# rev02_4.net
KiCad netlist of a schematic drawn in Altium Designer
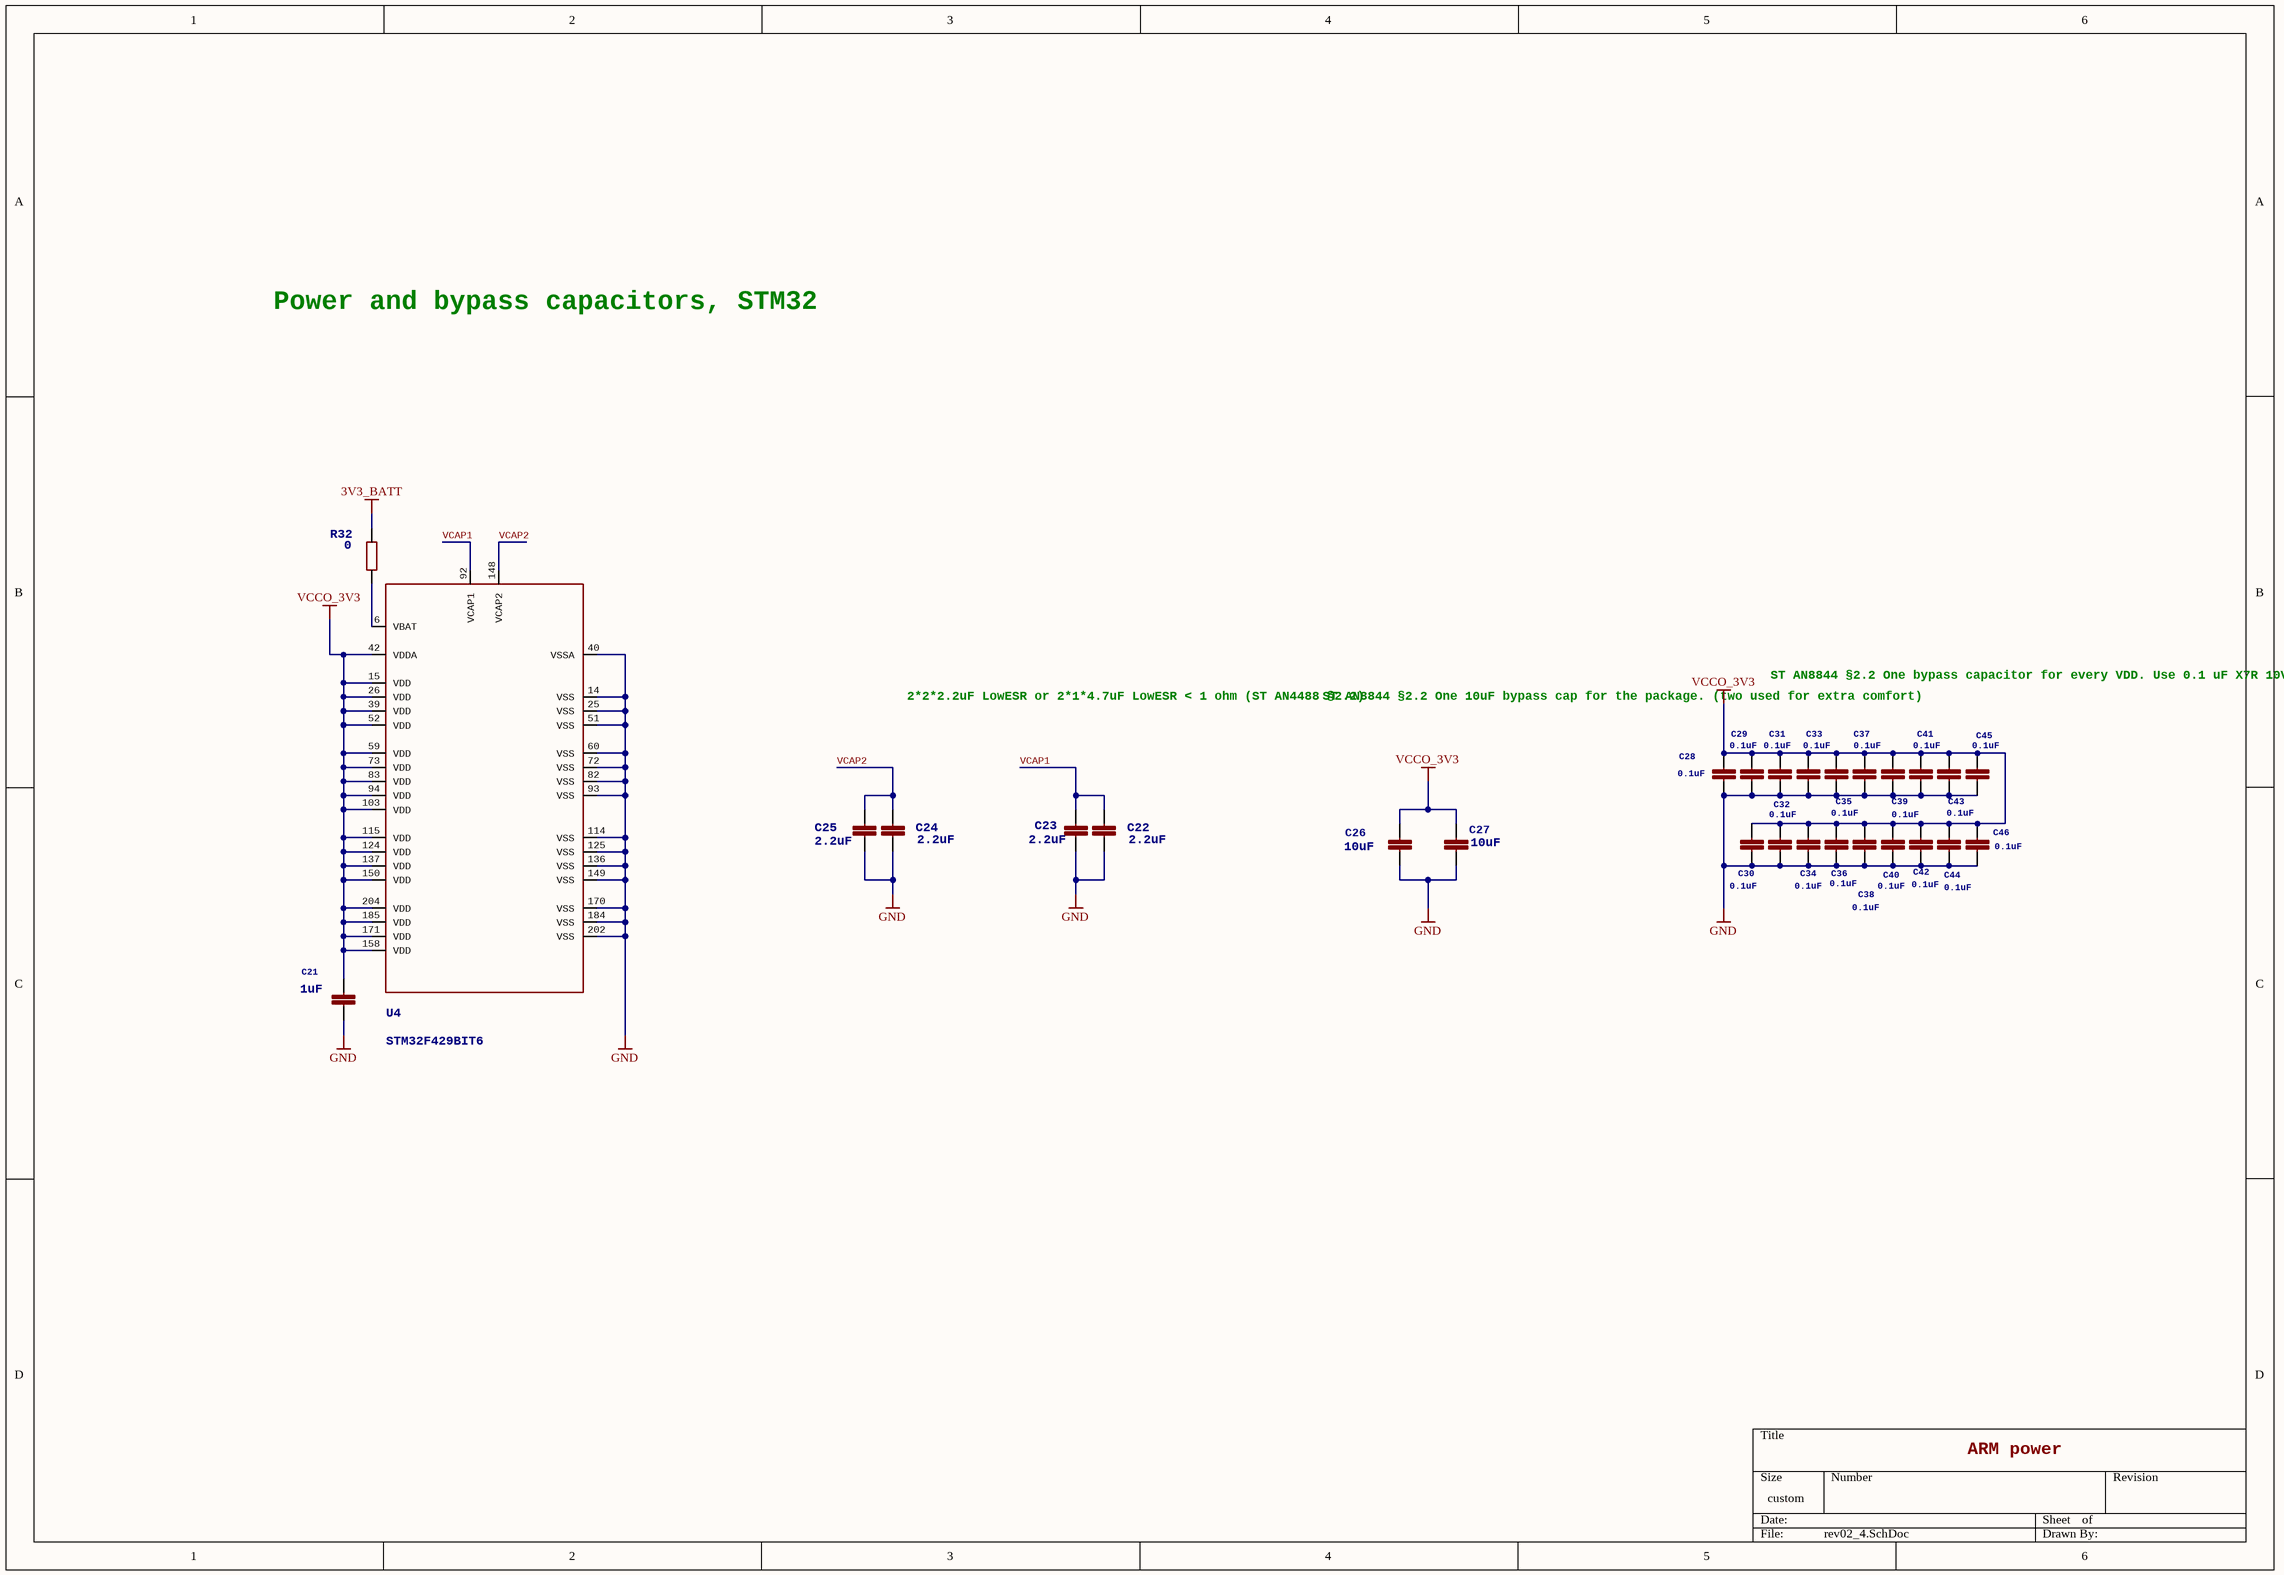
[diagram p0: rev02_4.SchDoc]

(export (version "E")
  (design (tool "Eeschema 10.0.6"))
  (components
    (comp (ref "C21")
      (value "1uF")
      (footprint "C_0603")
      (description "0603 CAPACITOR")
      (libsource (lib "") (part "C-EUC0603_1"))
    )
    (comp (ref "C22")
      (value "2.2uF")
      (footprint "C_0603")
      (description "0603 CAPACITOR")
      (libsource (lib "resistor") (part "C-EUC0603"))
    )
    (comp (ref "C23")
      (value "2.2uF")
      (footprint "C_0603")
      (description "0603 CAPACITOR")
      (libsource (lib "resistor") (part "C-EUC0603"))
    )
    (comp (ref "C24")
      (value "2.2uF")
      (footprint "C_0603")
      (description "0603 CAPACITOR")
      (libsource (lib "resistor") (part "C-EUC0603"))
    )
    (comp (ref "C25")
      (value "2.2uF")
      (footprint "C_0603")
      (description "0603 CAPACITOR")
      (libsource (lib "resistor") (part "C-EUC0603"))
    )
    (comp (ref "C26")
      (value "10uF")
      (footprint "C_0805")
      (description "0805 CAPACITOR")
      (libsource (lib "resistor") (part "C-EUC0805"))
    )
    (comp (ref "C27")
      (value "10uF")
      (footprint "C_0805")
      (description "0805 CAPACITOR")
      (libsource (lib "resistor") (part "C-EUC0805"))
    )
    (comp (ref "C28")
      (value "0.1uF")
      (footprint "C_0402")
      (description "0402 CAPACITOR")
      (libsource (lib "resistor") (part "C-EUC0402"))
    )
    (comp (ref "C29")
      (value "0.1uF")
      (footprint "C_0402")
      (description "0402 CAPACITOR")
      (libsource (lib "resistor") (part "C-EUC0402"))
    )
    (comp (ref "C30")
      (value "0.1uF")
      (footprint "C_0402")
      (description "0402 CAPACITOR")
      (libsource (lib "resistor") (part "C-EUC0402"))
    )
    (comp (ref "C31")
      (value "0.1uF")
      (footprint "C_0402")
      (description "0402 CAPACITOR")
      (libsource (lib "resistor") (part "C-EUC0402"))
    )
    (comp (ref "C32")
      (value "0.1uF")
      (footprint "C_0402")
      (description "0402 CAPACITOR")
      (libsource (lib "resistor") (part "C-EUC0402"))
    )
    (comp (ref "C33")
      (value "0.1uF")
      (footprint "C_0402")
      (description "0402 CAPACITOR")
      (libsource (lib "resistor") (part "C-EUC0402"))
    )
    (comp (ref "C34")
      (value "0.1uF")
      (footprint "C_0402")
      (description "0402 CAPACITOR")
      (libsource (lib "resistor") (part "C-EUC0402"))
    )
    (comp (ref "C35")
      (value "0.1uF")
      (footprint "C_0402")
      (description "0402 CAPACITOR")
      (libsource (lib "resistor") (part "C-EUC0402"))
    )
    (comp (ref "C36")
      (value "0.1uF")
      (footprint "C_0402")
      (description "0402 CAPACITOR")
      (libsource (lib "resistor") (part "C-EUC0402"))
    )
    (comp (ref "C37")
      (value "0.1uF")
      (footprint "C_0402")
      (description "0402 CAPACITOR")
      (libsource (lib "resistor") (part "C-EUC0402"))
    )
    (comp (ref "C38")
      (value "0.1uF")
      (footprint "C_0402")
      (description "0402 CAPACITOR")
      (libsource (lib "resistor") (part "C-EUC0402"))
    )
    (comp (ref "C39")
      (value "0.1uF")
      (footprint "C_0402")
      (description "0402 CAPACITOR")
      (libsource (lib "resistor") (part "C-EUC0402"))
    )
    (comp (ref "C40")
      (value "0.1uF")
      (footprint "C_0402")
      (description "0402 CAPACITOR")
      (libsource (lib "resistor") (part "C-EUC0402"))
    )
    (comp (ref "C41")
      (value "0.1uF")
      (footprint "C_0402")
      (description "0402 CAPACITOR")
      (libsource (lib "resistor") (part "C-EUC0402"))
    )
    (comp (ref "C42")
      (value "0.1uF")
      (footprint "C_0402")
      (description "0402 CAPACITOR")
      (libsource (lib "resistor") (part "C-EUC0402"))
    )
    (comp (ref "C43")
      (value "0.1uF")
      (footprint "C_0402")
      (description "0402 CAPACITOR")
      (libsource (lib "resistor") (part "C-EUC0402"))
    )
    (comp (ref "C44")
      (value "0.1uF")
      (footprint "C_0402")
      (description "0402 CAPACITOR")
      (libsource (lib "resistor") (part "C-EUC0402"))
    )
    (comp (ref "C45")
      (value "0.1uF")
      (footprint "C_0402")
      (description "0402 CAPACITOR")
      (libsource (lib "resistor") (part "C-EUC0402"))
    )
    (comp (ref "C46")
      (value "0.1uF")
      (footprint "C_0402")
      (description "0402 CAPACITOR")
      (libsource (lib "resistor") (part "C-EUC0402"))
    )
    (comp (ref "R32")
      (value "0")
      (footprint "R_0402")
      (description "0402 Resistor 5%")
      (libsource (lib "resistor") (part "R-EU_R0402"))
    )
    (comp (ref "U4")
      (value "STM32F429BIT6")
      (description "STM32F429 Cortex-M4 CPU\n180 MHz, 256 KB RAM, 2 MB Flash")
      (fields (field (name ">NAME") "U4") (field (name ">VALUE") "STM32F429BIT6"))
      (libsource (lib "Alpha-IC") (part "STM32F429BIT6"))
    )
  )
  (nets
    (net (code "1") (name "/VCAP1") (class "Default")
      (node (ref "C22") (pin "2") (pinfunction "2_2") (pintype "passive"))
      (node (ref "C23") (pin "2") (pinfunction "2_2") (pintype "passive"))
      (node (ref "U4") (pin "92") (pinfunction "VCAP1_92") (pintype "passive"))
    )
    (net (code "2") (name "/VCAP2") (class "Default")
      (node (ref "C24") (pin "2") (pinfunction "2_2") (pintype "passive"))
      (node (ref "C25") (pin "2") (pinfunction "2_2") (pintype "passive"))
      (node (ref "U4") (pin "148") (pinfunction "VCAP2_148") (pintype "passive"))
    )
    (net (code "3") (name "3V3_BATT") (class "Default")
      (node (ref "R32") (pin "1") (pinfunction "1_1") (pintype "passive"))
    )
    (net (code "4") (name "GND") (class "Default")
      (node (ref "C21") (pin "2") (pinfunction "2_2") (pintype "passive"))
      (node (ref "C22") (pin "1") (pinfunction "1_1") (pintype "passive"))
      (node (ref "C23") (pin "1") (pinfunction "1_1") (pintype "passive"))
      (node (ref "C24") (pin "1") (pinfunction "1_1") (pintype "passive"))
      (node (ref "C25") (pin "1") (pinfunction "1_1") (pintype "passive"))
      (node (ref "C26") (pin "2") (pinfunction "2_2") (pintype "passive"))
      (node (ref "C27") (pin "2") (pinfunction "2_2") (pintype "passive"))
      (node (ref "C28") (pin "2") (pinfunction "2_2") (pintype "passive"))
      (node (ref "C29") (pin "2") (pinfunction "2_2") (pintype "passive"))
      (node (ref "C30") (pin "2") (pinfunction "2_2") (pintype "passive"))
      (node (ref "C31") (pin "2") (pinfunction "2_2") (pintype "passive"))
      (node (ref "C32") (pin "2") (pinfunction "2_2") (pintype "passive"))
      (node (ref "C33") (pin "2") (pinfunction "2_2") (pintype "passive"))
      (node (ref "C34") (pin "2") (pinfunction "2_2") (pintype "passive"))
      (node (ref "C35") (pin "2") (pinfunction "2_2") (pintype "passive"))
      (node (ref "C36") (pin "2") (pinfunction "2_2") (pintype "passive"))
      (node (ref "C37") (pin "2") (pinfunction "2_2") (pintype "passive"))
      (node (ref "C38") (pin "2") (pinfunction "2_2") (pintype "passive"))
      (node (ref "C39") (pin "2") (pinfunction "2_2") (pintype "passive"))
      (node (ref "C40") (pin "2") (pinfunction "2_2") (pintype "passive"))
      (node (ref "C41") (pin "2") (pinfunction "2_2") (pintype "passive"))
      (node (ref "C42") (pin "2") (pinfunction "2_2") (pintype "passive"))
      (node (ref "C43") (pin "2") (pinfunction "2_2") (pintype "passive"))
      (node (ref "C44") (pin "2") (pinfunction "2_2") (pintype "passive"))
      (node (ref "C45") (pin "2") (pinfunction "2_2") (pintype "passive"))
      (node (ref "C46") (pin "2") (pinfunction "2_2") (pintype "passive"))
      (node (ref "U4") (pin "114") (pinfunction "VSS_114") (pintype "power_in"))
      (node (ref "U4") (pin "125") (pinfunction "VSS_125") (pintype "power_in"))
      (node (ref "U4") (pin "136") (pinfunction "VSS_136") (pintype "power_in"))
      (node (ref "U4") (pin "14") (pinfunction "VSS_14") (pintype "power_in"))
      (node (ref "U4") (pin "149") (pinfunction "VSS_149") (pintype "power_in"))
      (node (ref "U4") (pin "170") (pinfunction "VSS_170") (pintype "power_in"))
      (node (ref "U4") (pin "184") (pinfunction "VSS_184") (pintype "power_in"))
      (node (ref "U4") (pin "202") (pinfunction "VSS_202") (pintype "power_in"))
      (node (ref "U4") (pin "25") (pinfunction "VSS_25") (pintype "power_in"))
      (node (ref "U4") (pin "40") (pinfunction "VSSA_40") (pintype "power_in"))
      (node (ref "U4") (pin "51") (pinfunction "VSS_51") (pintype "power_in"))
      (node (ref "U4") (pin "60") (pinfunction "VSS_60") (pintype "power_in"))
      (node (ref "U4") (pin "72") (pinfunction "VSS_72") (pintype "power_in"))
      (node (ref "U4") (pin "82") (pinfunction "VSS_82") (pintype "power_in"))
      (node (ref "U4") (pin "93") (pinfunction "VSS_93") (pintype "power_in"))
    )
    (net (code "5") (name "Net-(U4C-VBAT)") (class "Default")
      (node (ref "R32") (pin "2") (pinfunction "2_2") (pintype "passive"))
      (node (ref "U4") (pin "6") (pinfunction "VBAT_6") (pintype "power_in"))
    )
    (net (code "6") (name "VCCO_3V3") (class "Default")
      (node (ref "C21") (pin "1") (pinfunction "1_1") (pintype "passive"))
      (node (ref "C26") (pin "1") (pinfunction "1_1") (pintype "passive"))
      (node (ref "C27") (pin "1") (pinfunction "1_1") (pintype "passive"))
      (node (ref "C28") (pin "1") (pinfunction "1_1") (pintype "passive"))
      (node (ref "C29") (pin "1") (pinfunction "1_1") (pintype "passive"))
      (node (ref "C30") (pin "1") (pinfunction "1_1") (pintype "passive"))
      (node (ref "C31") (pin "1") (pinfunction "1_1") (pintype "passive"))
      (node (ref "C32") (pin "1") (pinfunction "1_1") (pintype "passive"))
      (node (ref "C33") (pin "1") (pinfunction "1_1") (pintype "passive"))
      (node (ref "C34") (pin "1") (pinfunction "1_1") (pintype "passive"))
      (node (ref "C35") (pin "1") (pinfunction "1_1") (pintype "passive"))
      (node (ref "C36") (pin "1") (pinfunction "1_1") (pintype "passive"))
      (node (ref "C37") (pin "1") (pinfunction "1_1") (pintype "passive"))
      (node (ref "C38") (pin "1") (pinfunction "1_1") (pintype "passive"))
      (node (ref "C39") (pin "1") (pinfunction "1_1") (pintype "passive"))
      (node (ref "C40") (pin "1") (pinfunction "1_1") (pintype "passive"))
      (node (ref "C41") (pin "1") (pinfunction "1_1") (pintype "passive"))
      (node (ref "C42") (pin "1") (pinfunction "1_1") (pintype "passive"))
      (node (ref "C43") (pin "1") (pinfunction "1_1") (pintype "passive"))
      (node (ref "C44") (pin "1") (pinfunction "1_1") (pintype "passive"))
      (node (ref "C45") (pin "1") (pinfunction "1_1") (pintype "passive"))
      (node (ref "C46") (pin "1") (pinfunction "1_1") (pintype "passive"))
      (node (ref "U4") (pin "103") (pinfunction "VDD_103") (pintype "power_in"))
      (node (ref "U4") (pin "115") (pinfunction "VDD_115") (pintype "power_in"))
      (node (ref "U4") (pin "124") (pinfunction "VDD_124") (pintype "power_in"))
      (node (ref "U4") (pin "137") (pinfunction "VDD_137") (pintype "power_in"))
      (node (ref "U4") (pin "15") (pinfunction "VDD_15") (pintype "power_in"))
      (node (ref "U4") (pin "150") (pinfunction "VDD_150") (pintype "power_in"))
      (node (ref "U4") (pin "158") (pinfunction "VDD_158") (pintype "power_in"))
      (node (ref "U4") (pin "171") (pinfunction "VDD_171") (pintype "power_in"))
      (node (ref "U4") (pin "185") (pinfunction "VDD_185") (pintype "power_in"))
      (node (ref "U4") (pin "204") (pinfunction "VDD_204") (pintype "power_in"))
      (node (ref "U4") (pin "26") (pinfunction "VDD_26") (pintype "power_in"))
      (node (ref "U4") (pin "39") (pinfunction "VDD_39") (pintype "power_in"))
      (node (ref "U4") (pin "42") (pinfunction "VDDA_42") (pintype "power_in"))
      (node (ref "U4") (pin "52") (pinfunction "VDD_52") (pintype "power_in"))
      (node (ref "U4") (pin "59") (pinfunction "VDD_59") (pintype "power_in"))
      (node (ref "U4") (pin "73") (pinfunction "VDD_73") (pintype "power_in"))
      (node (ref "U4") (pin "83") (pinfunction "VDD_83") (pintype "power_in"))
      (node (ref "U4") (pin "94") (pinfunction "VDD_94") (pintype "power_in"))
    )
  )
)
